# adapters.net
KiCad netlist of a schematic drawn in EAGLE
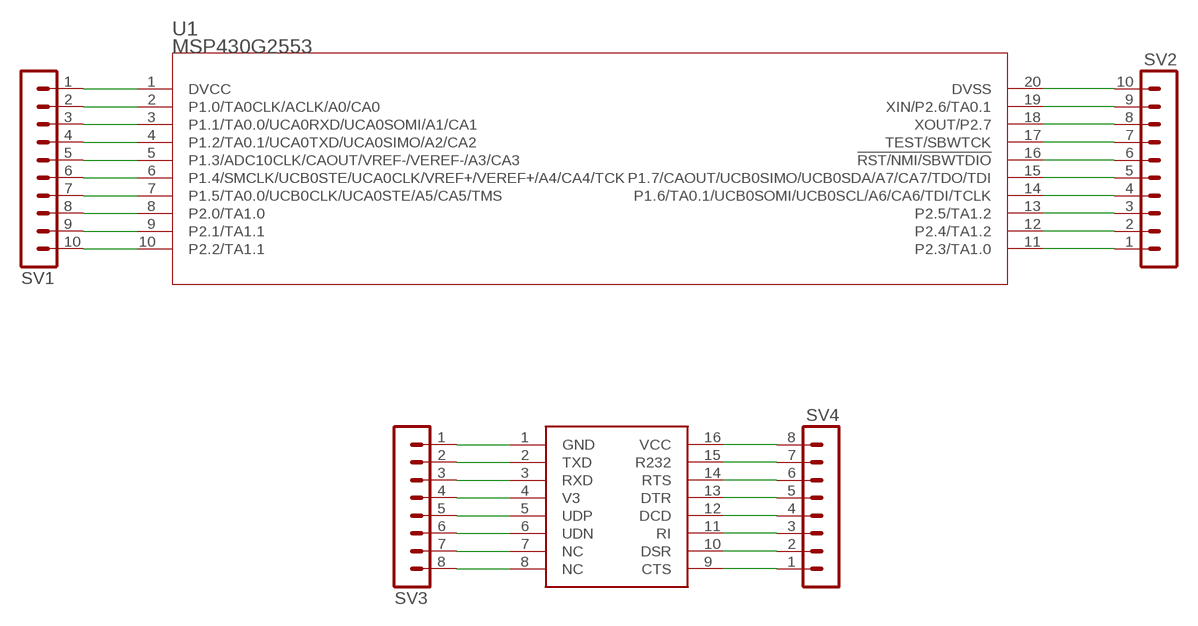
[diagram p0: schematic, sheet 1]

(export (version "E")
  (design (tool "Eeschema 10.0.6"))
  (components
    (comp (ref "SV1")
      (value "MA10-1")
      (footprint "eagle-import:MA10-1")
      (libsource (lib "eagle-import") (part "MA10-1"))
    )
    (comp (ref "SV2")
      (value "MA10-1")
      (footprint "eagle-import:MA10-1")
      (libsource (lib "eagle-import") (part "MA10-1"))
    )
    (comp (ref "SV3")
      (value "MA08-1")
      (footprint "eagle-import:MA08-1")
      (libsource (lib "eagle-import") (part "MA08-1"))
    )
    (comp (ref "SV4")
      (value "MA08-1")
      (footprint "eagle-import:MA08-1")
      (libsource (lib "eagle-import") (part "MA08-1"))
    )
    (comp (ref "U$1")
      (value "CH340")
      (footprint "eagle-import:SOP16")
      (libsource (lib "eagle-import") (part "CH340"))
    )
    (comp (ref "U1")
      (value "MSP430G2553")
      (footprint "eagle-import:PW20-M")
      (fields
        (field (name "MANUFACTURER_PART_NUMBER") "MSP430G2553IPW20R")
        (field (name "COPYRIGHT") "Copyright (C) 2023 Ultra Librarian. All rights reserved.")
      )
      (libsource (lib "eagle-import") (part "MSP430G2553IPW20RPW20-M"))
    )
  )
  (nets
    (net (code "1") (name "Net-(SV3-Pad7)") (class "Default")
      (node (ref "SV3") (pin "7") (pinfunction "7_7") (pintype "passive"))
      (node (ref "U$1") (pin "7") (pinfunction "NC_7") (pintype "bidirectional"))
    )
    (net (code "2") (name "Net-(SV3-Pad8)") (class "Default")
      (node (ref "SV3") (pin "8") (pinfunction "8_8") (pintype "passive"))
      (node (ref "U$1") (pin "8") (pinfunction "NC_8") (pintype "bidirectional"))
    )
    (net (code "3") (name "Net-(U$1-CTS)") (class "Default")
      (node (ref "SV4") (pin "1") (pinfunction "1_1") (pintype "passive"))
      (node (ref "U$1") (pin "9") (pinfunction "CTS_9") (pintype "bidirectional"))
    )
    (net (code "4") (name "Net-(U$1-DCD)") (class "Default")
      (node (ref "SV4") (pin "4") (pinfunction "4_4") (pintype "passive"))
      (node (ref "U$1") (pin "12") (pinfunction "DCD_12") (pintype "bidirectional"))
    )
    (net (code "5") (name "Net-(U$1-DSR)") (class "Default")
      (node (ref "SV4") (pin "2") (pinfunction "2_2") (pintype "passive"))
      (node (ref "U$1") (pin "10") (pinfunction "DSR_10") (pintype "bidirectional"))
    )
    (net (code "6") (name "Net-(U$1-DTR)") (class "Default")
      (node (ref "SV4") (pin "5") (pinfunction "5_5") (pintype "passive"))
      (node (ref "U$1") (pin "13") (pinfunction "DTR_13") (pintype "bidirectional"))
    )
    (net (code "7") (name "Net-(U$1-GND)") (class "Default")
      (node (ref "SV3") (pin "1") (pinfunction "1_1") (pintype "passive"))
      (node (ref "U$1") (pin "1") (pinfunction "GND_1") (pintype "bidirectional"))
    )
    (net (code "8") (name "Net-(U$1-R232)") (class "Default")
      (node (ref "SV4") (pin "7") (pinfunction "7_7") (pintype "passive"))
      (node (ref "U$1") (pin "15") (pinfunction "R232_15") (pintype "bidirectional"))
    )
    (net (code "9") (name "Net-(U$1-RI)") (class "Default")
      (node (ref "SV4") (pin "3") (pinfunction "3_3") (pintype "passive"))
      (node (ref "U$1") (pin "11") (pinfunction "RI_11") (pintype "bidirectional"))
    )
    (net (code "10") (name "Net-(U$1-RTS)") (class "Default")
      (node (ref "SV4") (pin "6") (pinfunction "6_6") (pintype "passive"))
      (node (ref "U$1") (pin "14") (pinfunction "RTS_14") (pintype "bidirectional"))
    )
    (net (code "11") (name "Net-(U$1-RXD)") (class "Default")
      (node (ref "SV3") (pin "3") (pinfunction "3_3") (pintype "passive"))
      (node (ref "U$1") (pin "3") (pinfunction "RXD_3") (pintype "bidirectional"))
    )
    (net (code "12") (name "Net-(U$1-TXD)") (class "Default")
      (node (ref "SV3") (pin "2") (pinfunction "2_2") (pintype "passive"))
      (node (ref "U$1") (pin "2") (pinfunction "TXD_2") (pintype "bidirectional"))
    )
    (net (code "13") (name "Net-(U$1-UDN)") (class "Default")
      (node (ref "SV3") (pin "6") (pinfunction "6_6") (pintype "passive"))
      (node (ref "U$1") (pin "6") (pinfunction "UDN_6") (pintype "bidirectional"))
    )
    (net (code "14") (name "Net-(U$1-UDP)") (class "Default")
      (node (ref "SV3") (pin "5") (pinfunction "5_5") (pintype "passive"))
      (node (ref "U$1") (pin "5") (pinfunction "UDP_5") (pintype "bidirectional"))
    )
    (net (code "15") (name "Net-(U$1-V3)") (class "Default")
      (node (ref "SV3") (pin "4") (pinfunction "4_4") (pintype "passive"))
      (node (ref "U$1") (pin "4") (pinfunction "V3_4") (pintype "bidirectional"))
    )
    (net (code "16") (name "Net-(U$1-VCC)") (class "Default")
      (node (ref "SV4") (pin "8") (pinfunction "8_8") (pintype "passive"))
      (node (ref "U$1") (pin "16") (pinfunction "VCC_16") (pintype "bidirectional"))
    )
    (net (code "17") (name "Net-(U1-DVCC)") (class "Default")
      (node (ref "SV1") (pin "1") (pinfunction "1_1") (pintype "passive"))
      (node (ref "U1") (pin "1") (pinfunction "DVCC_1") (pintype "power_in"))
    )
    (net (code "18") (name "Net-(U1-DVSS)") (class "Default")
      (node (ref "SV2") (pin "10") (pinfunction "10_10") (pintype "passive"))
      (node (ref "U1") (pin "20") (pinfunction "DVSS_20") (pintype "power_in"))
    )
    (net (code "19") (name "Net-(U1-P1.0{slash}TA0CLK{slash}ACLK{slash}A0{slash}CA0)") (class "Default")
      (node (ref "SV1") (pin "2") (pinfunction "2_2") (pintype "passive"))
      (node (ref "U1") (pin "2") (pinfunction "P1.0/TA0CLK/ACLK/A0/CA0_2") (pintype "bidirectional"))
    )
    (net (code "20") (name "Net-(U1-P1.1{slash}TA0.0{slash}UCA0RXD{slash}UCA0SOMI{slash}A1{slash}CA1)") (class "Default")
      (node (ref "SV1") (pin "3") (pinfunction "3_3") (pintype "passive"))
      (node (ref "U1") (pin "3") (pinfunction "P1.1/TA0.0/UCA0RXD/UCA0SOMI/A1/CA1_3") (pintype "bidirectional"))
    )
    (net (code "21") (name "Net-(U1-P1.2{slash}TA0.1{slash}UCA0TXD{slash}UCA0SIMO{slash}A2{slash}CA2)") (class "Default")
      (node (ref "SV1") (pin "4") (pinfunction "4_4") (pintype "passive"))
      (node (ref "U1") (pin "4") (pinfunction "P1.2/TA0.1/UCA0TXD/UCA0SIMO/A2/CA2_4") (pintype "bidirectional"))
    )
    (net (code "22") (name "Net-(U1-P1.3{slash}ADC10CLK{slash}CAOUT{slash}VREF-{slash}VEREF-{slash}A3{slash}CA3)") (class "Default")
      (node (ref "SV1") (pin "5") (pinfunction "5_5") (pintype "passive"))
      (node (ref "U1") (pin "5") (pinfunction "P1.3/ADC10CLK/CAOUT/VREF-/VEREF-/A3/CA3_5") (pintype "bidirectional"))
    )
    (net (code "23") (name "Net-(U1-P1.4{slash}SMCLK{slash}UCB0STE{slash}UCA0CLK{slash}VREF+{slash}VEREF+{slash}A4{slash}CA4{slash}TCK)") (class "Default")
      (node (ref "SV1") (pin "6") (pinfunction "6_6") (pintype "passive"))
      (node (ref "U1") (pin "6") (pinfunction "P1.4/SMCLK/UCB0STE/UCA0CLK/VREF+/VEREF+/A4/CA4/TCK_6") (pintype "bidirectional"))
    )
    (net (code "24") (name "Net-(U1-P1.5{slash}TA0.0{slash}UCB0CLK{slash}UCA0STE{slash}A5{slash}CA5{slash}TMS)") (class "Default")
      (node (ref "SV1") (pin "7") (pinfunction "7_7") (pintype "passive"))
      (node (ref "U1") (pin "7") (pinfunction "P1.5/TA0.0/UCB0CLK/UCA0STE/A5/CA5/TMS_7") (pintype "bidirectional"))
    )
    (net (code "25") (name "Net-(U1-P1.6{slash}TA0.1{slash}UCB0SOMI{slash}UCB0SCL{slash}A6{slash}CA6{slash}TDI{slash}TCLK)") (class "Default")
      (node (ref "SV2") (pin "4") (pinfunction "4_4") (pintype "passive"))
      (node (ref "U1") (pin "14") (pinfunction "P1.6/TA0.1/UCB0SOMI/UCB0SCL/A6/CA6/TDI/TCLK_14") (pintype "bidirectional"))
    )
    (net (code "26") (name "Net-(U1-P1.7{slash}CAOUT{slash}UCB0SIMO{slash}UCB0SDA{slash}A7{slash}CA7{slash}TDO{slash}TDI)") (class "Default")
      (node (ref "SV2") (pin "5") (pinfunction "5_5") (pintype "passive"))
      (node (ref "U1") (pin "15") (pinfunction "P1.7/CAOUT/UCB0SIMO/UCB0SDA/A7/CA7/TDO/TDI_15") (pintype "bidirectional"))
    )
    (net (code "27") (name "Net-(U1-P2.0{slash}TA1.0)") (class "Default")
      (node (ref "SV1") (pin "8") (pinfunction "8_8") (pintype "passive"))
      (node (ref "U1") (pin "8") (pinfunction "P2.0/TA1.0_8") (pintype "bidirectional"))
    )
    (net (code "28") (name "Net-(U1-P2.1{slash}TA1.1)") (class "Default")
      (node (ref "SV1") (pin "9") (pinfunction "9_9") (pintype "passive"))
      (node (ref "U1") (pin "9") (pinfunction "P2.1/TA1.1_9") (pintype "bidirectional"))
    )
    (net (code "29") (name "Net-(U1-P2.2{slash}TA1.1)") (class "Default")
      (node (ref "SV1") (pin "10") (pinfunction "10_10") (pintype "passive"))
      (node (ref "U1") (pin "10") (pinfunction "P2.2/TA1.1_10") (pintype "bidirectional"))
    )
    (net (code "30") (name "Net-(U1-P2.3{slash}TA1.0)") (class "Default")
      (node (ref "SV2") (pin "1") (pinfunction "1_1") (pintype "passive"))
      (node (ref "U1") (pin "11") (pinfunction "P2.3/TA1.0_11") (pintype "bidirectional"))
    )
    (net (code "31") (name "Net-(U1-P2.4{slash}TA1.2)") (class "Default")
      (node (ref "SV2") (pin "2") (pinfunction "2_2") (pintype "passive"))
      (node (ref "U1") (pin "12") (pinfunction "P2.4/TA1.2_12") (pintype "bidirectional"))
    )
    (net (code "32") (name "Net-(U1-P2.5{slash}TA1.2)") (class "Default")
      (node (ref "SV2") (pin "3") (pinfunction "3_3") (pintype "passive"))
      (node (ref "U1") (pin "13") (pinfunction "P2.5/TA1.2_13") (pintype "bidirectional"))
    )
    (net (code "33") (name "Net-(U1-TEST{slash}SBWTCK)") (class "Default")
      (node (ref "SV2") (pin "7") (pinfunction "7_7") (pintype "passive"))
      (node (ref "U1") (pin "17") (pinfunction "TEST/SBWTCK_17") (pintype "bidirectional"))
    )
    (net (code "34") (name "Net-(U1-XIN{slash}P2.6{slash}TA0.1)") (class "Default")
      (node (ref "SV2") (pin "9") (pinfunction "9_9") (pintype "passive"))
      (node (ref "U1") (pin "19") (pinfunction "XIN/P2.6/TA0.1_19") (pintype "bidirectional"))
    )
    (net (code "35") (name "Net-(U1-XOUT{slash}P2.7)") (class "Default")
      (node (ref "SV2") (pin "8") (pinfunction "8_8") (pintype "passive"))
      (node (ref "U1") (pin "18") (pinfunction "XOUT/P2.7_18") (pintype "bidirectional"))
    )
    (net (code "36") (name "Net-(U1-~{RST{slash}NMI{slash}SBWTDIO})") (class "Default")
      (node (ref "SV2") (pin "6") (pinfunction "6_6") (pintype "passive"))
      (node (ref "U1") (pin "16") (pinfunction "~{RST/NMI/SBWTDIO}_16") (pintype "bidirectional"))
    )
  )
)
